# POWER.net
KiCad netlist of a schematic drawn in Altium Designer
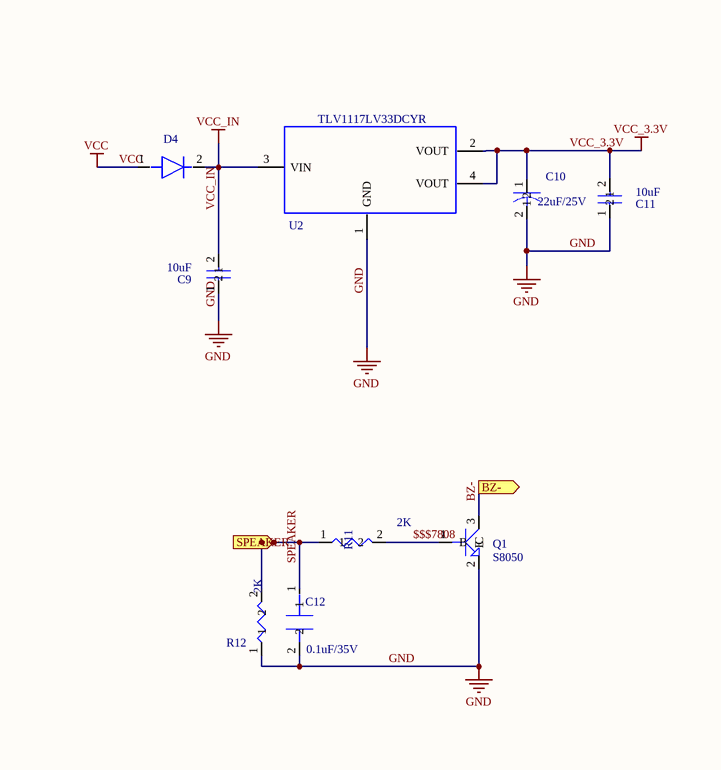
[diagram p0: POWER.SchDoc, top left]
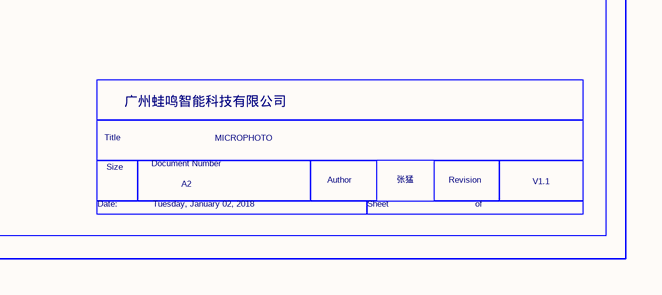
[diagram p1: POWER.SchDoc, bottom right]

(export (version "E")
  (design (tool "Eeschema 10.0.6"))
  (components
    (comp (ref "C9")
      (value "10uF")
      (fields (field (name "Comment") "EC0603"))
      (libsource (lib "*") (part "EC0603"))
    )
    (comp (ref "C10")
      (value "22uF/25V")
      (description "ALU CAP 100UF 10V 20%   DC-5X7MM")
      (fields (field (name "Comment") "EC1206"))
      (libsource (lib "*") (part "EC1206"))
    )
    (comp (ref "C11")
      (value "10uF")
      (fields (field (name "Comment") "EC0603"))
      (libsource (lib "*") (part "EC0603"))
    )
    (comp (ref "C12")
      (value "0.1uF/35V")
      (fields (field (name "Comment") "CAP"))
      (libsource (lib "*") (part "CAP"))
    )
    (comp (ref "D4")
      (value "DIODE")
      (description "GENERIC DIODE W ALTERNATE")
      (libsource (lib "*") (part "DIODE"))
    )
    (comp (ref "Q1") (value "S8050") (libsource (lib "*") (part "S8050")))
    (comp (ref "R11")
      (value "2K")
      (fields (field (name "Comment") "ER0402"))
      (libsource (lib "*") (part "ER0402"))
    )
    (comp (ref "R12")
      (value "2K")
      (fields (field (name "Comment") "ER0402"))
      (libsource (lib "*") (part "ER0402"))
    )
    (comp (ref "U2") (value "TLV1117LV33DCYR") (libsource (lib "*") (part "TLV1117LV33DCYR")))
  )
  (nets
    (net (code "1") (name "/$$$7808") (class "Default")
      (node (ref "Q1") (pin "1") (pinfunction "B_1") (pintype "passive"))
      (node (ref "R11") (pin "2") (pinfunction "2_2") (pintype "passive"))
    )
    (net (code "2") (name "/BZ-") (class "Default")
      (node (ref "Q1") (pin "3") (pinfunction "C_3") (pintype "passive"))
    )
    (net (code "3") (name "/SPEAKER") (class "Default")
      (node (ref "C12") (pin "1") (pinfunction "1_1") (pintype "passive"))
      (node (ref "R11") (pin "1") (pinfunction "1_1") (pintype "passive"))
      (node (ref "R12") (pin "2") (pinfunction "2_2") (pintype "passive"))
    )
    (net (code "4") (name "GND") (class "Default")
      (node (ref "C10") (pin "2") (pinfunction "2_2") (pintype "passive"))
      (node (ref "C11") (pin "1") (pinfunction "1_1") (pintype "passive"))
      (node (ref "C12") (pin "2") (pinfunction "2_2") (pintype "passive"))
      (node (ref "C9") (pin "1") (pinfunction "1_1") (pintype "passive"))
      (node (ref "Q1") (pin "2") (pinfunction "E_2") (pintype "passive"))
      (node (ref "R12") (pin "1") (pinfunction "1_1") (pintype "passive"))
      (node (ref "U2") (pin "1") (pinfunction "GND_1") (pintype "passive"))
    )
    (net (code "5") (name "VCC") (class "Default") (node (ref "D4") (pin "1") (pintype "passive")))
    (net (code "6") (name "VCC_3.3V") (class "Default")
      (node (ref "C10") (pin "1") (pinfunction "1_1") (pintype "passive"))
      (node (ref "C11") (pin "2") (pinfunction "2_2") (pintype "passive"))
      (node (ref "U2") (pin "2") (pinfunction "VOUT_2") (pintype "passive"))
      (node (ref "U2") (pin "4") (pinfunction "VOUT_4") (pintype "passive"))
    )
    (net (code "7") (name "VCC_IN") (class "Default")
      (node (ref "C9") (pin "2") (pinfunction "2_2") (pintype "passive"))
      (node (ref "D4") (pin "2") (pintype "passive"))
      (node (ref "U2") (pin "3") (pinfunction "VIN_3") (pintype "passive"))
    )
  )
)
